# thg-probe.net
KiCad netlist of a schematic drawn in EAGLE
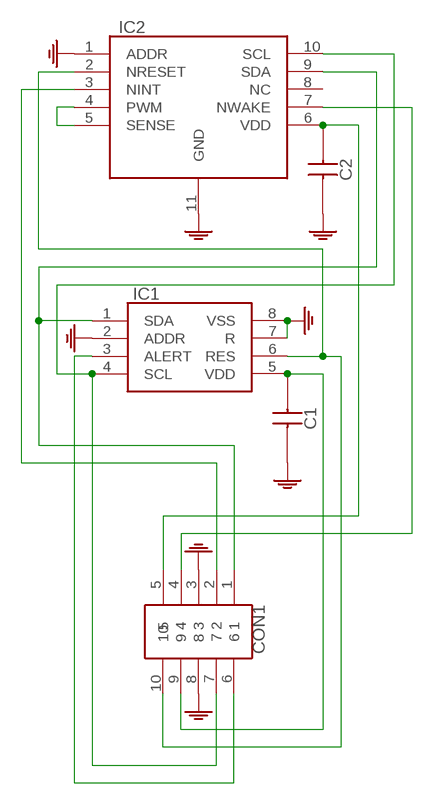
[diagram p0: schematic, sheet 1]

(export (version "E")
  (design (tool "Eeschema 10.0.6"))
  (components
    (comp (ref "C1")
      (value "CAPACITOR-0603")
      (footprint "eagle-import:0603")
      (libsource (lib "eagle-import") (part "CAPACITOR-0603"))
    )
    (comp (ref "C2")
      (value "CAPACITOR-0603")
      (footprint "eagle-import:0603")
      (libsource (lib "eagle-import") (part "CAPACITOR-0603"))
    )
    (comp (ref "CON1")
      (value "HEADER-10P-2R-DIP-2_54MM")
      (footprint "eagle-import:HEADER-10P-2R-DIP-2_54MM")
      (libsource (lib "eagle-import") (part "HEADER-10P-2R-DIP-2_54MM"))
    )
    (comp (ref "IC1")
      (value "SHT3X-DIS")
      (footprint "eagle-import:SHT3X-DIS")
      (libsource (lib "eagle-import") (part "SHT3X-DIS"))
    )
    (comp (ref "IC2")
      (value "CCS811B-JOPD500")
      (footprint "eagle-import:LGA-10")
      (libsource (lib "eagle-import") (part "CCS811B-JOPD500"))
    )
  )
  (nets
    (net (code "1") (name "GND") (class "Default")
      (node (ref "C1") (pin "2") (pinfunction "2_2") (pintype "passive"))
      (node (ref "C2") (pin "2") (pinfunction "2_2") (pintype "passive"))
      (node (ref "CON1") (pin "3") (pinfunction "3_3") (pintype "bidirectional"))
      (node (ref "CON1") (pin "8") (pinfunction "8_8") (pintype "bidirectional"))
      (node (ref "IC1") (pin "2") (pinfunction "ADDR_2") (pintype "bidirectional"))
      (node (ref "IC1") (pin "7") (pinfunction "R_7") (pintype "bidirectional"))
      (node (ref "IC1") (pin "8") (pinfunction "VSS_8") (pintype "bidirectional"))
      (node (ref "IC2") (pin "1") (pinfunction "ADDR_1") (pintype "bidirectional"))
      (node (ref "IC2") (pin "11") (pinfunction "GND_11") (pintype "power_in"))
    )
    (net (code "2") (name "Net-(IC1-ALERT)") (class "Default")
      (node (ref "CON1") (pin "6") (pinfunction "6_6") (pintype "bidirectional"))
      (node (ref "IC1") (pin "3") (pinfunction "ALERT_3") (pintype "bidirectional"))
    )
    (net (code "3") (name "Net-(IC1-RES)") (class "Default")
      (node (ref "CON1") (pin "10") (pinfunction "10_10") (pintype "bidirectional"))
      (node (ref "IC1") (pin "6") (pinfunction "RES_6") (pintype "bidirectional"))
      (node (ref "IC2") (pin "2") (pinfunction "NRESET_2") (pintype "bidirectional"))
    )
    (net (code "4") (name "Net-(IC1-SCL)") (class "Default")
      (node (ref "CON1") (pin "7") (pinfunction "7_7") (pintype "bidirectional"))
      (node (ref "IC1") (pin "4") (pinfunction "SCL_4") (pintype "bidirectional"))
      (node (ref "IC2") (pin "10") (pinfunction "SCL_10") (pintype "bidirectional"))
    )
    (net (code "5") (name "Net-(IC1-SDA)") (class "Default")
      (node (ref "CON1") (pin "1") (pinfunction "1_1") (pintype "bidirectional"))
      (node (ref "IC1") (pin "1") (pinfunction "SDA_1") (pintype "bidirectional"))
      (node (ref "IC2") (pin "9") (pinfunction "SDA_9") (pintype "bidirectional"))
    )
    (net (code "6") (name "Net-(IC1-VDD)") (class "Default")
      (node (ref "C1") (pin "1") (pinfunction "1_1") (pintype "passive"))
      (node (ref "CON1") (pin "9") (pinfunction "9_9") (pintype "bidirectional"))
      (node (ref "IC1") (pin "5") (pinfunction "VDD_5") (pintype "power_in"))
    )
    (net (code "7") (name "Net-(IC2-NINT)") (class "Default")
      (node (ref "CON1") (pin "2") (pinfunction "2_2") (pintype "bidirectional"))
      (node (ref "IC2") (pin "3") (pinfunction "NINT_3") (pintype "bidirectional"))
    )
    (net (code "8") (name "Net-(IC2-NWAKE)") (class "Default")
      (node (ref "CON1") (pin "4") (pinfunction "4_4") (pintype "bidirectional"))
      (node (ref "IC2") (pin "7") (pinfunction "NWAKE_7") (pintype "bidirectional"))
    )
    (net (code "9") (name "Net-(IC2-PWM)") (class "Default")
      (node (ref "IC2") (pin "4") (pinfunction "PWM_4") (pintype "bidirectional"))
      (node (ref "IC2") (pin "5") (pinfunction "SENSE_5") (pintype "bidirectional"))
    )
    (net (code "10") (name "Net-(IC2-VDD)") (class "Default")
      (node (ref "C2") (pin "1") (pinfunction "1_1") (pintype "passive"))
      (node (ref "CON1") (pin "5") (pinfunction "5_5") (pintype "bidirectional"))
      (node (ref "IC2") (pin "6") (pinfunction "VDD_6") (pintype "power_in"))
    )
    (net (code "11") (name "unconnected-(IC2-NC-Pad8)") (class "Default")
      (node (ref "IC2") (pin "8") (pinfunction "NC_8") (pintype "no_connect"))
    )
  )
)
